# ExtensionConnector.net
KiCad netlist of a schematic drawn in Altium Designer
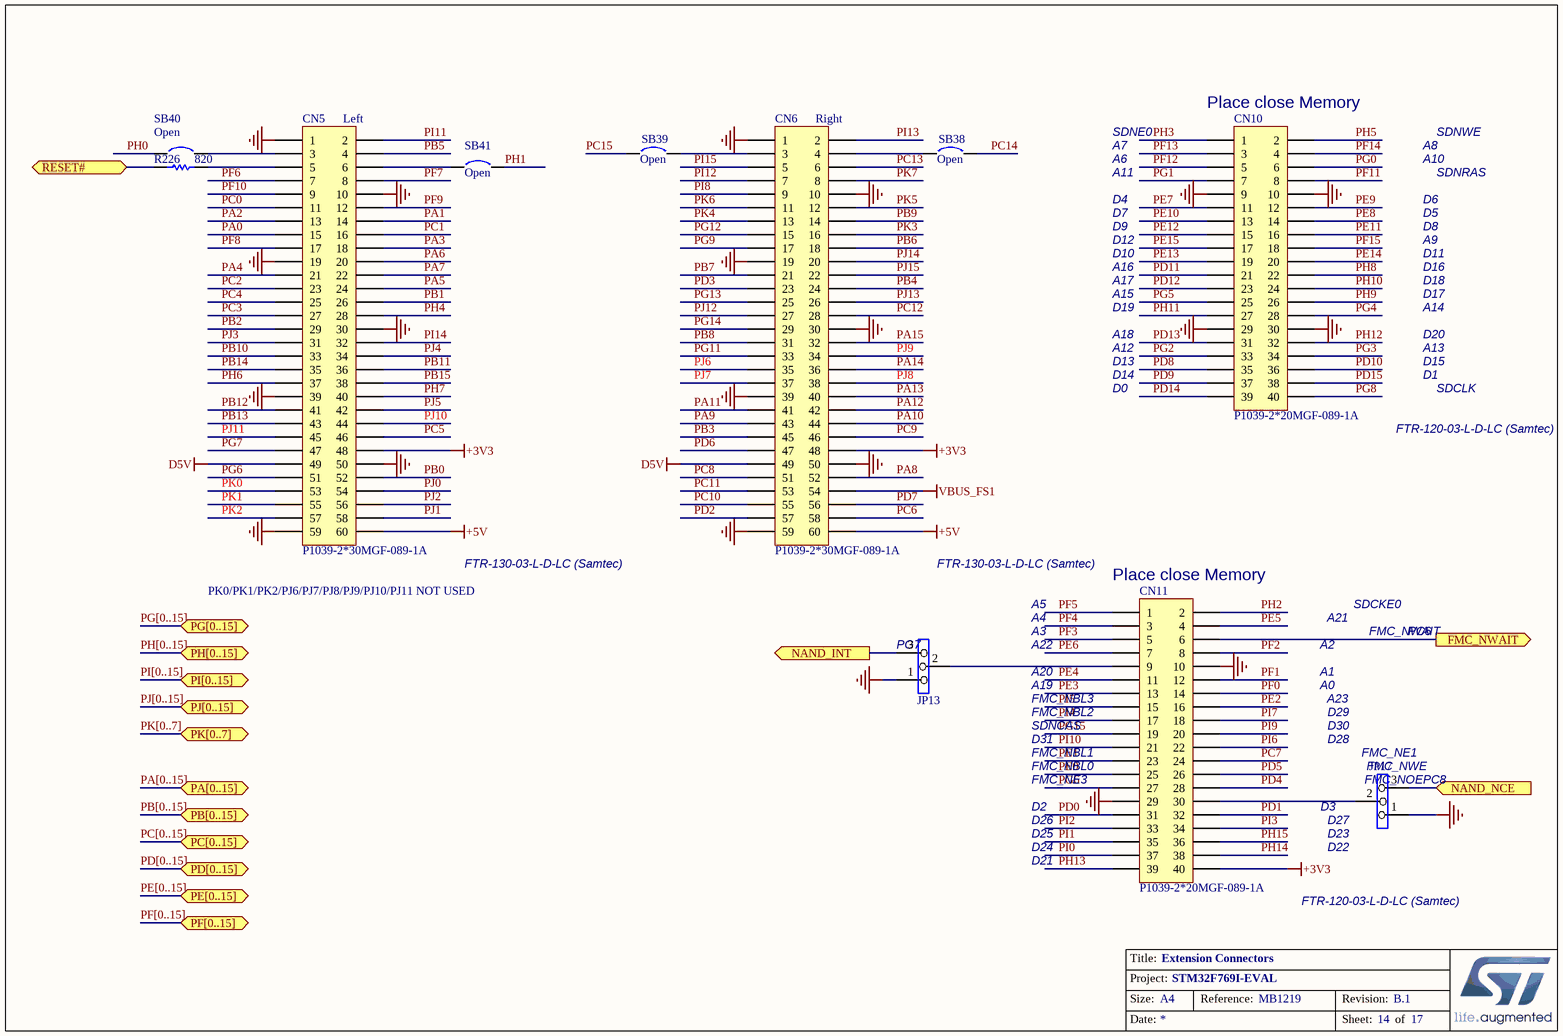
[diagram p0: ExtensionConnector.SchDoc]

(export (version "E")
  (design (tool "Eeschema 10.0.6"))
  (components
    (comp (ref "CN5")
      (value "P1039-2*30MGF-089-1A")
      (footprint "FTR-130-53-L-D-LC")
      (description "Header, 40-Pin, Dual row")
      (fields (field (name "PUBLISHER") "Altium Limited"))
      (libsource (lib "mb1045") (part "FTR-130-53-L-D-LC"))
    )
    (comp (ref "CN6")
      (value "P1039-2*30MGF-089-1A")
      (footprint "FTR-130-53-L-D-LC")
      (description "Header, 40-Pin, Dual row")
      (fields (field (name "PUBLISHER") "Altium Limited"))
      (libsource (lib "mb1045") (part "FTR-130-53-L-D-LC"))
    )
    (comp (ref "CN10")
      (value "P1039-2*20MGF-089-1A")
      (footprint "FTR-120-53-L-D-LC")
      (description "Header, 20-Pin, Dual row")
      (fields (field (name "PUBLISHER") "Altium Limited"))
      (libsource (lib "mb1045") (part "FTR-120-53-L-D-LC"))
    )
    (comp (ref "CN11")
      (value "P1039-2*20MGF-089-1A")
      (footprint "FTR-120-53-L-D-LC")
      (description "Header, 20-Pin, Dual row")
      (fields (field (name "PUBLISHER") "Altium Limited"))
      (libsource (lib "mb1045") (part "FTR-120-53-L-D-LC"))
    )
    (comp (ref "JP13") (value "~") (footprint "SIP3") (libsource (lib "STR910_SCHLIB") (part "Jumper3")))
    (comp (ref "JP17") (value "~") (footprint "SIP3") (libsource (lib "STR910_SCHLIB") (part "Jumper3")))
    (comp (ref "R226")
      (value "820")
      (footprint "0603R")
      (description "Resistor")
      (fields (field (name "PUBLISHER") "Altium Limited"))
      (libsource (lib "Miscellaneous Devices") (part "res1"))
    )
    (comp (ref "SB38")
      (value "Open")
      (footprint "SB_0603")
      (description "Circuit Breaker")
      (fields (field (name "PUBLISHER") "Altium Limited"))
      (libsource (lib "") (part "Circuit Breaker_1"))
    )
    (comp (ref "SB39")
      (value "Open")
      (footprint "SB_0603")
      (description "Circuit Breaker")
      (fields (field (name "PUBLISHER") "Altium Limited"))
      (libsource (lib "MB1167") (part "Circuit Breaker"))
    )
    (comp (ref "SB40")
      (value "Open")
      (footprint "SB_0603")
      (description "Circuit Breaker")
      (fields (field (name "PUBLISHER") "Altium Limited"))
      (libsource (lib "MB1167") (part "Circuit Breaker"))
    )
    (comp (ref "SB41")
      (value "Open")
      (footprint "SB_0603")
      (description "Circuit Breaker")
      (fields (field (name "PUBLISHER") "Altium Limited"))
      (libsource (lib "") (part "Circuit Breaker_1"))
    )
  )
  (nets
    (net (code "2") (name "+3V3") (class "Default")
      (node (ref "CN11") (pin "40") (pinfunction "40_40") (pintype "passive"))
      (node (ref "CN5") (pin "48") (pinfunction "48_48") (pintype "passive"))
      (node (ref "CN6") (pin "48") (pinfunction "48_48") (pintype "passive"))
    )
    (net (code "3") (name "+5V") (class "Default")
      (node (ref "CN5") (pin "60") (pinfunction "60_60") (pintype "passive"))
      (node (ref "CN6") (pin "60") (pinfunction "60_60") (pintype "passive"))
    )
    (net (code "4") (name "/FMC_NWAIT") (class "Default")
      (node (ref "CN11") (pin "6") (pinfunction "6_6") (pintype "passive"))
    )
    (net (code "5") (name "/NAND_INT") (class "Default") (node (ref "JP13") (pin "3") (pintype "passive")))
    (net (code "6") (name "/NAND_NCE") (class "Default") (node (ref "JP17") (pin "3") (pintype "passive")))
    (net (code "7") (name "/PA0") (class "Default")
      (node (ref "CN5") (pin "15") (pinfunction "15_15") (pintype "passive"))
    )
    (net (code "8") (name "/PA1") (class "Default")
      (node (ref "CN5") (pin "14") (pinfunction "14_14") (pintype "passive"))
    )
    (net (code "9") (name "/PA2") (class "Default")
      (node (ref "CN5") (pin "13") (pinfunction "13_13") (pintype "passive"))
    )
    (net (code "10") (name "/PA3") (class "Default")
      (node (ref "CN5") (pin "18") (pinfunction "18_18") (pintype "passive"))
    )
    (net (code "11") (name "/PA4") (class "Default")
      (node (ref "CN5") (pin "21") (pinfunction "21_21") (pintype "passive"))
    )
    (net (code "12") (name "/PA5") (class "Default")
      (node (ref "CN5") (pin "24") (pinfunction "24_24") (pintype "passive"))
    )
    (net (code "13") (name "/PA6") (class "Default")
      (node (ref "CN5") (pin "20") (pinfunction "20_20") (pintype "passive"))
    )
    (net (code "14") (name "/PA7") (class "Default")
      (node (ref "CN5") (pin "22") (pinfunction "22_22") (pintype "passive"))
    )
    (net (code "15") (name "/PA8") (class "Default")
      (node (ref "CN6") (pin "52") (pinfunction "52_52") (pintype "passive"))
    )
    (net (code "16") (name "/PA9") (class "Default")
      (node (ref "CN6") (pin "43") (pinfunction "43_43") (pintype "passive"))
    )
    (net (code "17") (name "/PA10") (class "Default")
      (node (ref "CN6") (pin "44") (pinfunction "44_44") (pintype "passive"))
    )
    (net (code "18") (name "/PA11") (class "Default")
      (node (ref "CN6") (pin "41") (pinfunction "41_41") (pintype "passive"))
    )
    (net (code "19") (name "/PA12") (class "Default")
      (node (ref "CN6") (pin "42") (pinfunction "42_42") (pintype "passive"))
    )
    (net (code "20") (name "/PA13") (class "Default")
      (node (ref "CN6") (pin "40") (pinfunction "40_40") (pintype "passive"))
    )
    (net (code "21") (name "/PA14") (class "Default")
      (node (ref "CN6") (pin "36") (pinfunction "36_36") (pintype "passive"))
    )
    (net (code "22") (name "/PA15") (class "Default")
      (node (ref "CN6") (pin "32") (pinfunction "32_32") (pintype "passive"))
    )
    (net (code "24") (name "/PB0") (class "Default")
      (node (ref "CN5") (pin "52") (pinfunction "52_52") (pintype "passive"))
    )
    (net (code "25") (name "/PB1") (class "Default")
      (node (ref "CN5") (pin "26") (pinfunction "26_26") (pintype "passive"))
    )
    (net (code "26") (name "/PB2") (class "Default")
      (node (ref "CN5") (pin "29") (pinfunction "29_29") (pintype "passive"))
    )
    (net (code "27") (name "/PB3") (class "Default")
      (node (ref "CN6") (pin "45") (pinfunction "45_45") (pintype "passive"))
    )
    (net (code "28") (name "/PB4") (class "Default")
      (node (ref "CN6") (pin "24") (pinfunction "24_24") (pintype "passive"))
    )
    (net (code "29") (name "/PB5") (class "Default")
      (node (ref "CN5") (pin "4") (pinfunction "4_4") (pintype "passive"))
    )
    (net (code "30") (name "/PB6") (class "Default")
      (node (ref "CN6") (pin "18") (pinfunction "18_18") (pintype "passive"))
    )
    (net (code "31") (name "/PB7") (class "Default")
      (node (ref "CN6") (pin "21") (pinfunction "21_21") (pintype "passive"))
    )
    (net (code "32") (name "/PB8") (class "Default")
      (node (ref "CN6") (pin "31") (pinfunction "31_31") (pintype "passive"))
    )
    (net (code "33") (name "/PB9") (class "Default")
      (node (ref "CN6") (pin "14") (pinfunction "14_14") (pintype "passive"))
    )
    (net (code "34") (name "/PB10") (class "Default")
      (node (ref "CN5") (pin "33") (pinfunction "33_33") (pintype "passive"))
    )
    (net (code "35") (name "/PB11") (class "Default")
      (node (ref "CN5") (pin "36") (pinfunction "36_36") (pintype "passive"))
    )
    (net (code "36") (name "/PB12") (class "Default")
      (node (ref "CN5") (pin "41") (pinfunction "41_41") (pintype "passive"))
    )
    (net (code "37") (name "/PB13") (class "Default")
      (node (ref "CN5") (pin "43") (pinfunction "43_43") (pintype "passive"))
    )
    (net (code "38") (name "/PB14") (class "Default")
      (node (ref "CN5") (pin "35") (pinfunction "35_35") (pintype "passive"))
    )
    (net (code "39") (name "/PB15") (class "Default")
      (node (ref "CN5") (pin "38") (pinfunction "38_38") (pintype "passive"))
    )
    (net (code "41") (name "/PC0") (class "Default")
      (node (ref "CN5") (pin "11") (pinfunction "11_11") (pintype "passive"))
    )
    (net (code "42") (name "/PC1") (class "Default")
      (node (ref "CN5") (pin "16") (pinfunction "16_16") (pintype "passive"))
    )
    (net (code "43") (name "/PC2") (class "Default")
      (node (ref "CN5") (pin "23") (pinfunction "23_23") (pintype "passive"))
    )
    (net (code "44") (name "/PC3") (class "Default")
      (node (ref "CN5") (pin "27") (pinfunction "27_27") (pintype "passive"))
    )
    (net (code "45") (name "/PC4") (class "Default")
      (node (ref "CN5") (pin "25") (pinfunction "25_25") (pintype "passive"))
    )
    (net (code "46") (name "/PC5") (class "Default")
      (node (ref "CN5") (pin "46") (pinfunction "46_46") (pintype "passive"))
    )
    (net (code "47") (name "/PC6") (class "Default")
      (node (ref "CN6") (pin "58") (pinfunction "58_58") (pintype "passive"))
    )
    (net (code "48") (name "/PC7") (class "Default")
      (node (ref "CN11") (pin "24") (pinfunction "24_24") (pintype "passive"))
    )
    (net (code "49") (name "/PC8") (class "Default")
      (node (ref "CN6") (pin "51") (pinfunction "51_51") (pintype "passive"))
    )
    (net (code "50") (name "/PC9") (class "Default")
      (node (ref "CN6") (pin "46") (pinfunction "46_46") (pintype "passive"))
    )
    (net (code "51") (name "/PC10") (class "Default")
      (node (ref "CN6") (pin "55") (pinfunction "55_55") (pintype "passive"))
    )
    (net (code "52") (name "/PC11") (class "Default")
      (node (ref "CN6") (pin "53") (pinfunction "53_53") (pintype "passive"))
    )
    (net (code "53") (name "/PC12") (class "Default")
      (node (ref "CN6") (pin "28") (pinfunction "28_28") (pintype "passive"))
    )
    (net (code "54") (name "/PC13") (class "Default")
      (node (ref "CN6") (pin "6") (pinfunction "6_6") (pintype "passive"))
    )
    (net (code "55") (name "/PC14") (class "Default")
      (node (ref "SB38") (pin "1") (pinfunction "1_1") (pintype "passive"))
    )
    (net (code "56") (name "/PC15") (class "Default")
      (node (ref "SB39") (pin "1") (pinfunction "1_1") (pintype "passive"))
    )
    (net (code "58") (name "/PD0") (class "Default")
      (node (ref "CN11") (pin "31") (pinfunction "31_31") (pintype "passive"))
    )
    (net (code "59") (name "/PD1") (class "Default")
      (node (ref "CN11") (pin "32") (pinfunction "32_32") (pintype "passive"))
    )
    (net (code "60") (name "/PD2") (class "Default")
      (node (ref "CN6") (pin "57") (pinfunction "57_57") (pintype "passive"))
    )
    (net (code "61") (name "/PD3") (class "Default")
      (node (ref "CN6") (pin "23") (pinfunction "23_23") (pintype "passive"))
    )
    (net (code "62") (name "/PD4") (class "Default")
      (node (ref "CN11") (pin "28") (pinfunction "28_28") (pintype "passive"))
    )
    (net (code "63") (name "/PD5") (class "Default")
      (node (ref "CN11") (pin "26") (pinfunction "26_26") (pintype "passive"))
    )
    (net (code "64") (name "/PD6") (class "Default")
      (node (ref "CN6") (pin "47") (pinfunction "47_47") (pintype "passive"))
    )
    (net (code "65") (name "/PD7") (class "Default")
      (node (ref "CN6") (pin "56") (pinfunction "56_56") (pintype "passive"))
    )
    (net (code "66") (name "/PD8") (class "Default")
      (node (ref "CN10") (pin "35") (pinfunction "35_35") (pintype "passive"))
    )
    (net (code "67") (name "/PD9") (class "Default")
      (node (ref "CN10") (pin "37") (pinfunction "37_37") (pintype "passive"))
    )
    (net (code "68") (name "/PD10") (class "Default")
      (node (ref "CN10") (pin "36") (pinfunction "36_36") (pintype "passive"))
    )
    (net (code "69") (name "/PD11") (class "Default")
      (node (ref "CN10") (pin "21") (pinfunction "21_21") (pintype "passive"))
    )
    (net (code "70") (name "/PD12") (class "Default")
      (node (ref "CN10") (pin "23") (pinfunction "23_23") (pintype "passive"))
    )
    (net (code "71") (name "/PD13") (class "Default")
      (node (ref "CN10") (pin "31") (pinfunction "31_31") (pintype "passive"))
    )
    (net (code "72") (name "/PD14") (class "Default")
      (node (ref "CN10") (pin "39") (pinfunction "39_39") (pintype "passive"))
    )
    (net (code "73") (name "/PD15") (class "Default")
      (node (ref "CN10") (pin "38") (pinfunction "38_38") (pintype "passive"))
    )
    (net (code "75") (name "/PE0") (class "Default")
      (node (ref "CN11") (pin "25") (pinfunction "25_25") (pintype "passive"))
    )
    (net (code "76") (name "/PE1") (class "Default")
      (node (ref "CN11") (pin "23") (pinfunction "23_23") (pintype "passive"))
    )
    (net (code "77") (name "/PE2") (class "Default")
      (node (ref "CN11") (pin "16") (pinfunction "16_16") (pintype "passive"))
    )
    (net (code "78") (name "/PE3") (class "Default")
      (node (ref "CN11") (pin "13") (pinfunction "13_13") (pintype "passive"))
    )
    (net (code "79") (name "/PE4") (class "Default")
      (node (ref "CN11") (pin "11") (pinfunction "11_11") (pintype "passive"))
    )
    (net (code "80") (name "/PE5") (class "Default")
      (node (ref "CN11") (pin "4") (pinfunction "4_4") (pintype "passive"))
    )
    (net (code "81") (name "/PE6") (class "Default")
      (node (ref "CN11") (pin "7") (pinfunction "7_7") (pintype "passive"))
    )
    (net (code "82") (name "/PE7") (class "Default")
      (node (ref "CN10") (pin "11") (pinfunction "11_11") (pintype "passive"))
    )
    (net (code "83") (name "/PE8") (class "Default")
      (node (ref "CN10") (pin "14") (pinfunction "14_14") (pintype "passive"))
    )
    (net (code "84") (name "/PE9") (class "Default")
      (node (ref "CN10") (pin "12") (pinfunction "12_12") (pintype "passive"))
    )
    (net (code "85") (name "/PE10") (class "Default")
      (node (ref "CN10") (pin "13") (pinfunction "13_13") (pintype "passive"))
    )
    (net (code "86") (name "/PE11") (class "Default")
      (node (ref "CN10") (pin "16") (pinfunction "16_16") (pintype "passive"))
    )
    (net (code "87") (name "/PE12") (class "Default")
      (node (ref "CN10") (pin "15") (pinfunction "15_15") (pintype "passive"))
    )
    (net (code "88") (name "/PE13") (class "Default")
      (node (ref "CN10") (pin "19") (pinfunction "19_19") (pintype "passive"))
    )
    (net (code "89") (name "/PE14") (class "Default")
      (node (ref "CN10") (pin "20") (pinfunction "20_20") (pintype "passive"))
    )
    (net (code "90") (name "/PE15") (class "Default")
      (node (ref "CN10") (pin "17") (pinfunction "17_17") (pintype "passive"))
    )
    (net (code "92") (name "/PF0") (class "Default")
      (node (ref "CN11") (pin "14") (pinfunction "14_14") (pintype "passive"))
    )
    (net (code "93") (name "/PF1") (class "Default")
      (node (ref "CN11") (pin "12") (pinfunction "12_12") (pintype "passive"))
    )
    (net (code "94") (name "/PF2") (class "Default")
      (node (ref "CN11") (pin "8") (pinfunction "8_8") (pintype "passive"))
    )
    (net (code "95") (name "/PF3") (class "Default")
      (node (ref "CN11") (pin "5") (pinfunction "5_5") (pintype "passive"))
    )
    (net (code "96") (name "/PF4") (class "Default")
      (node (ref "CN11") (pin "3") (pinfunction "3_3") (pintype "passive"))
    )
    (net (code "97") (name "/PF5") (class "Default")
      (node (ref "CN11") (pin "1") (pinfunction "1_1") (pintype "passive"))
    )
    (net (code "98") (name "/PF6") (class "Default")
      (node (ref "CN5") (pin "7") (pinfunction "7_7") (pintype "passive"))
    )
    (net (code "99") (name "/PF7") (class "Default")
      (node (ref "CN5") (pin "8") (pinfunction "8_8") (pintype "passive"))
    )
    (net (code "100") (name "/PF8") (class "Default")
      (node (ref "CN5") (pin "17") (pinfunction "17_17") (pintype "passive"))
    )
    (net (code "101") (name "/PF9") (class "Default")
      (node (ref "CN5") (pin "12") (pinfunction "12_12") (pintype "passive"))
    )
    (net (code "102") (name "/PF10") (class "Default")
      (node (ref "CN5") (pin "9") (pinfunction "9_9") (pintype "passive"))
    )
    (net (code "103") (name "/PF11") (class "Default")
      (node (ref "CN10") (pin "8") (pinfunction "8_8") (pintype "passive"))
    )
    (net (code "104") (name "/PF12") (class "Default")
      (node (ref "CN10") (pin "5") (pinfunction "5_5") (pintype "passive"))
    )
    (net (code "105") (name "/PF13") (class "Default")
      (node (ref "CN10") (pin "3") (pinfunction "3_3") (pintype "passive"))
    )
    (net (code "106") (name "/PF14") (class "Default")
      (node (ref "CN10") (pin "4") (pinfunction "4_4") (pintype "passive"))
    )
    (net (code "107") (name "/PF15") (class "Default")
      (node (ref "CN10") (pin "18") (pinfunction "18_18") (pintype "passive"))
    )
    (net (code "109") (name "/PG0") (class "Default")
      (node (ref "CN10") (pin "6") (pinfunction "6_6") (pintype "passive"))
    )
    (net (code "110") (name "/PG1") (class "Default")
      (node (ref "CN10") (pin "7") (pinfunction "7_7") (pintype "passive"))
    )
    (net (code "111") (name "/PG2") (class "Default")
      (node (ref "CN10") (pin "33") (pinfunction "33_33") (pintype "passive"))
    )
    (net (code "112") (name "/PG3") (class "Default")
      (node (ref "CN10") (pin "34") (pinfunction "34_34") (pintype "passive"))
    )
    (net (code "113") (name "/PG4") (class "Default")
      (node (ref "CN10") (pin "28") (pinfunction "28_28") (pintype "passive"))
    )
    (net (code "114") (name "/PG5") (class "Default")
      (node (ref "CN10") (pin "25") (pinfunction "25_25") (pintype "passive"))
    )
    (net (code "115") (name "/PG6") (class "Default")
      (node (ref "CN11") (pin "27") (pinfunction "27_27") (pintype "passive"))
      (node (ref "CN5") (pin "51") (pinfunction "51_51") (pintype "passive"))
    )
    (net (code "116") (name "/PG7") (class "Default")
      (node (ref "CN5") (pin "47") (pinfunction "47_47") (pintype "passive"))
    )
    (net (code "117") (name "/PG8") (class "Default")
      (node (ref "CN10") (pin "40") (pinfunction "40_40") (pintype "passive"))
    )
    (net (code "118") (name "/PG9") (class "Default")
      (node (ref "CN6") (pin "17") (pinfunction "17_17") (pintype "passive"))
    )
    (net (code "119") (name "/PG11") (class "Default")
      (node (ref "CN6") (pin "33") (pinfunction "33_33") (pintype "passive"))
    )
    (net (code "120") (name "/PG12") (class "Default")
      (node (ref "CN6") (pin "15") (pinfunction "15_15") (pintype "passive"))
    )
    (net (code "121") (name "/PG13") (class "Default")
      (node (ref "CN6") (pin "25") (pinfunction "25_25") (pintype "passive"))
    )
    (net (code "122") (name "/PG14") (class "Default")
      (node (ref "CN6") (pin "29") (pinfunction "29_29") (pintype "passive"))
    )
    (net (code "123") (name "/PG15") (class "Default")
      (node (ref "CN11") (pin "19") (pinfunction "19_19") (pintype "passive"))
    )
    (net (code "125") (name "/PH0") (class "Default")
      (node (ref "SB40") (pin "1") (pinfunction "1_1") (pintype "passive"))
    )
    (net (code "126") (name "/PH1") (class "Default")
      (node (ref "SB41") (pin "1") (pinfunction "1_1") (pintype "passive"))
    )
    (net (code "127") (name "/PH2") (class "Default")
      (node (ref "CN11") (pin "2") (pinfunction "2_2") (pintype "passive"))
    )
    (net (code "128") (name "/PH3") (class "Default")
      (node (ref "CN10") (pin "1") (pinfunction "1_1") (pintype "passive"))
    )
    (net (code "129") (name "/PH4") (class "Default")
      (node (ref "CN5") (pin "28") (pinfunction "28_28") (pintype "passive"))
    )
    (net (code "130") (name "/PH5") (class "Default")
      (node (ref "CN10") (pin "2") (pinfunction "2_2") (pintype "passive"))
    )
    (net (code "131") (name "/PH6") (class "Default")
      (node (ref "CN5") (pin "37") (pinfunction "37_37") (pintype "passive"))
    )
    (net (code "132") (name "/PH7") (class "Default")
      (node (ref "CN5") (pin "40") (pinfunction "40_40") (pintype "passive"))
    )
    (net (code "133") (name "/PH8") (class "Default")
      (node (ref "CN10") (pin "22") (pinfunction "22_22") (pintype "passive"))
    )
    (net (code "134") (name "/PH9") (class "Default")
      (node (ref "CN10") (pin "26") (pinfunction "26_26") (pintype "passive"))
    )
    (net (code "135") (name "/PH10") (class "Default")
      (node (ref "CN10") (pin "24") (pinfunction "24_24") (pintype "passive"))
    )
    (net (code "136") (name "/PH11") (class "Default")
      (node (ref "CN10") (pin "27") (pinfunction "27_27") (pintype "passive"))
    )
    (net (code "137") (name "/PH12") (class "Default")
      (node (ref "CN10") (pin "32") (pinfunction "32_32") (pintype "passive"))
    )
    (net (code "138") (name "/PH13") (class "Default")
      (node (ref "CN11") (pin "39") (pinfunction "39_39") (pintype "passive"))
    )
    (net (code "139") (name "/PH14") (class "Default")
      (node (ref "CN11") (pin "38") (pinfunction "38_38") (pintype "passive"))
    )
    (net (code "140") (name "/PH15") (class "Default")
      (node (ref "CN11") (pin "36") (pinfunction "36_36") (pintype "passive"))
    )
    (net (code "142") (name "/PI0") (class "Default")
      (node (ref "CN11") (pin "37") (pinfunction "37_37") (pintype "passive"))
    )
    (net (code "143") (name "/PI1") (class "Default")
      (node (ref "CN11") (pin "35") (pinfunction "35_35") (pintype "passive"))
    )
    (net (code "144") (name "/PI2") (class "Default")
      (node (ref "CN11") (pin "33") (pinfunction "33_33") (pintype "passive"))
    )
    (net (code "145") (name "/PI3") (class "Default")
      (node (ref "CN11") (pin "34") (pinfunction "34_34") (pintype "passive"))
    )
    (net (code "146") (name "/PI4") (class "Default")
      (node (ref "CN11") (pin "17") (pinfunction "17_17") (pintype "passive"))
    )
    (net (code "147") (name "/PI5") (class "Default")
      (node (ref "CN11") (pin "15") (pinfunction "15_15") (pintype "passive"))
    )
    (net (code "148") (name "/PI6") (class "Default")
      (node (ref "CN11") (pin "22") (pinfunction "22_22") (pintype "passive"))
    )
    (net (code "149") (name "/PI7") (class "Default")
      (node (ref "CN11") (pin "18") (pinfunction "18_18") (pintype "passive"))
    )
    (net (code "150") (name "/PI8") (class "Default")
      (node (ref "CN6") (pin "9") (pinfunction "9_9") (pintype "passive"))
    )
    (net (code "151") (name "/PI9") (class "Default")
      (node (ref "CN11") (pin "20") (pinfunction "20_20") (pintype "passive"))
    )
    (net (code "152") (name "/PI10") (class "Default")
      (node (ref "CN11") (pin "21") (pinfunction "21_21") (pintype "passive"))
    )
    (net (code "153") (name "/PI11") (class "Default")
      (node (ref "CN5") (pin "2") (pinfunction "2_2") (pintype "passive"))
    )
    (net (code "154") (name "/PI12") (class "Default")
      (node (ref "CN6") (pin "7") (pinfunction "7_7") (pintype "passive"))
    )
    (net (code "155") (name "/PI13") (class "Default")
      (node (ref "CN6") (pin "2") (pinfunction "2_2") (pintype "passive"))
    )
    (net (code "156") (name "/PI14") (class "Default")
      (node (ref "CN5") (pin "32") (pinfunction "32_32") (pintype "passive"))
    )
    (net (code "157") (name "/PI15") (class "Default")
      (node (ref "CN6") (pin "5") (pinfunction "5_5") (pintype "passive"))
    )
    (net (code "159") (name "/PJ0") (class "Default")
      (node (ref "CN5") (pin "54") (pinfunction "54_54") (pintype "passive"))
    )
    (net (code "160") (name "/PJ1") (class "Default")
      (node (ref "CN5") (pin "58") (pinfunction "58_58") (pintype "passive"))
    )
    (net (code "161") (name "/PJ2") (class "Default")
      (node (ref "CN5") (pin "56") (pinfunction "56_56") (pintype "passive"))
    )
    (net (code "162") (name "/PJ3") (class "Default")
      (node (ref "CN5") (pin "31") (pinfunction "31_31") (pintype "passive"))
    )
    (net (code "163") (name "/PJ4") (class "Default")
      (node (ref "CN5") (pin "34") (pinfunction "34_34") (pintype "passive"))
    )
    (net (code "164") (name "/PJ5") (class "Default")
      (node (ref "CN5") (pin "42") (pinfunction "42_42") (pintype "passive"))
    )
    (net (code "165") (name "/PJ6") (class "Default")
      (node (ref "CN6") (pin "35") (pinfunction "35_35") (pintype "passive"))
    )
    (net (code "166") (name "/PJ7") (class "Default")
      (node (ref "CN6") (pin "37") (pinfunction "37_37") (pintype "passive"))
    )
    (net (code "167") (name "/PJ8") (class "Default")
      (node (ref "CN6") (pin "38") (pinfunction "38_38") (pintype "passive"))
    )
    (net (code "168") (name "/PJ9") (class "Default")
      (node (ref "CN6") (pin "34") (pinfunction "34_34") (pintype "passive"))
    )
    (net (code "169") (name "/PJ10") (class "Default")
      (node (ref "CN5") (pin "44") (pinfunction "44_44") (pintype "passive"))
    )
    (net (code "170") (name "/PJ11") (class "Default")
      (node (ref "CN5") (pin "45") (pinfunction "45_45") (pintype "passive"))
    )
    (net (code "171") (name "/PJ12") (class "Default")
      (node (ref "CN6") (pin "27") (pinfunction "27_27") (pintype "passive"))
    )
    (net (code "172") (name "/PJ13") (class "Default")
      (node (ref "CN6") (pin "26") (pinfunction "26_26") (pintype "passive"))
    )
    (net (code "173") (name "/PJ14") (class "Default")
      (node (ref "CN6") (pin "20") (pinfunction "20_20") (pintype "passive"))
    )
    (net (code "174") (name "/PJ15") (class "Default")
      (node (ref "CN6") (pin "22") (pinfunction "22_22") (pintype "passive"))
    )
    (net (code "176") (name "/PK0") (class "Default")
      (node (ref "CN5") (pin "53") (pinfunction "53_53") (pintype "passive"))
    )
    (net (code "177") (name "/PK1") (class "Default")
      (node (ref "CN5") (pin "55") (pinfunction "55_55") (pintype "passive"))
    )
    (net (code "178") (name "/PK2") (class "Default")
      (node (ref "CN5") (pin "57") (pinfunction "57_57") (pintype "passive"))
    )
    (net (code "179") (name "/PK3") (class "Default")
      (node (ref "CN6") (pin "16") (pinfunction "16_16") (pintype "passive"))
    )
    (net (code "180") (name "/PK4") (class "Default")
      (node (ref "CN6") (pin "13") (pinfunction "13_13") (pintype "passive"))
    )
    (net (code "181") (name "/PK5") (class "Default")
      (node (ref "CN6") (pin "12") (pinfunction "12_12") (pintype "passive"))
    )
    (net (code "182") (name "/PK6") (class "Default")
      (node (ref "CN6") (pin "11") (pinfunction "11_11") (pintype "passive"))
    )
    (net (code "183") (name "/PK7") (class "Default")
      (node (ref "CN6") (pin "8") (pinfunction "8_8") (pintype "passive"))
    )
    (net (code "185") (name "/RESET#") (class "Default")
      (node (ref "R226") (pin "1") (pinfunction "1_1") (pintype "passive"))
    )
    (net (code "186") (name "D5V") (class "Default")
      (node (ref "CN5") (pin "49") (pinfunction "49_49") (pintype "passive"))
      (node (ref "CN6") (pin "49") (pinfunction "49_49") (pintype "passive"))
    )
    (net (code "187") (name "GND") (class "Default")
      (node (ref "CN10") (pin "10") (pinfunction "10_10") (pintype "passive"))
      (node (ref "CN10") (pin "29") (pinfunction "29_29") (pintype "passive"))
      (node (ref "CN10") (pin "30") (pinfunction "30_30") (pintype "passive"))
      (node (ref "CN10") (pin "9") (pinfunction "9_9") (pintype "passive"))
      (node (ref "CN11") (pin "10") (pinfunction "10_10") (pintype "passive"))
      (node (ref "CN11") (pin "29") (pinfunction "29_29") (pintype "passive"))
      (node (ref "CN5") (pin "1") (pinfunction "1_1") (pintype "passive"))
      (node (ref "CN5") (pin "10") (pinfunction "10_10") (pintype "passive"))
      (node (ref "CN5") (pin "19") (pinfunction "19_19") (pintype "passive"))
      (node (ref "CN5") (pin "30") (pinfunction "30_30") (pintype "passive"))
      (node (ref "CN5") (pin "39") (pinfunction "39_39") (pintype "passive"))
      (node (ref "CN5") (pin "50") (pinfunction "50_50") (pintype "passive"))
      (node (ref "CN5") (pin "59") (pinfunction "59_59") (pintype "passive"))
      (node (ref "CN6") (pin "1") (pinfunction "1_1") (pintype "passive"))
      (node (ref "CN6") (pin "10") (pinfunction "10_10") (pintype "passive"))
      (node (ref "CN6") (pin "19") (pinfunction "19_19") (pintype "passive"))
      (node (ref "CN6") (pin "30") (pinfunction "30_30") (pintype "passive"))
      (node (ref "CN6") (pin "39") (pinfunction "39_39") (pintype "passive"))
      (node (ref "CN6") (pin "50") (pinfunction "50_50") (pintype "passive"))
      (node (ref "CN6") (pin "59") (pinfunction "59_59") (pintype "passive"))
      (node (ref "JP13") (pin "1") (pintype "passive"))
      (node (ref "JP17") (pin "1") (pintype "passive"))
    )
    (net (code "188") (name "Net-(CN5-Pad3)") (class "Default")
      (node (ref "CN5") (pin "3") (pinfunction "3_3") (pintype "passive"))
      (node (ref "SB40") (pin "2") (pinfunction "2_2") (pintype "passive"))
    )
    (net (code "189") (name "Net-(CN5-Pad5)") (class "Default")
      (node (ref "CN5") (pin "5") (pinfunction "5_5") (pintype "passive"))
      (node (ref "R226") (pin "2") (pinfunction "2_2") (pintype "passive"))
    )
    (net (code "190") (name "Net-(CN5-Pad6)") (class "Default")
      (node (ref "CN5") (pin "6") (pinfunction "6_6") (pintype "passive"))
      (node (ref "SB41") (pin "2") (pinfunction "2_2") (pintype "passive"))
    )
    (net (code "191") (name "Net-(CN6-Pad3)") (class "Default")
      (node (ref "CN6") (pin "3") (pinfunction "3_3") (pintype "passive"))
      (node (ref "SB39") (pin "2") (pinfunction "2_2") (pintype "passive"))
    )
    (net (code "192") (name "Net-(CN6-Pad4)") (class "Default")
      (node (ref "CN6") (pin "4") (pinfunction "4_4") (pintype "passive"))
      (node (ref "SB38") (pin "2") (pinfunction "2_2") (pintype "passive"))
    )
    (net (code "193") (name "Net-(CN11-Pad9)") (class "Default")
      (node (ref "CN11") (pin "9") (pinfunction "9_9") (pintype "passive"))
      (node (ref "JP13") (pin "2") (pintype "passive"))
    )
    (net (code "194") (name "Net-(CN11-Pad30)") (class "Default")
      (node (ref "CN11") (pin "30") (pinfunction "30_30") (pintype "passive"))
      (node (ref "JP17") (pin "2") (pintype "passive"))
    )
    (net (code "195") (name "VBUS_FS1") (class "Default")
      (node (ref "CN6") (pin "54") (pinfunction "54_54") (pintype "passive"))
    )
  )
)
